# Door_PCB_MAIN.net
KiCad netlist of a schematic drawn in Altium Designer
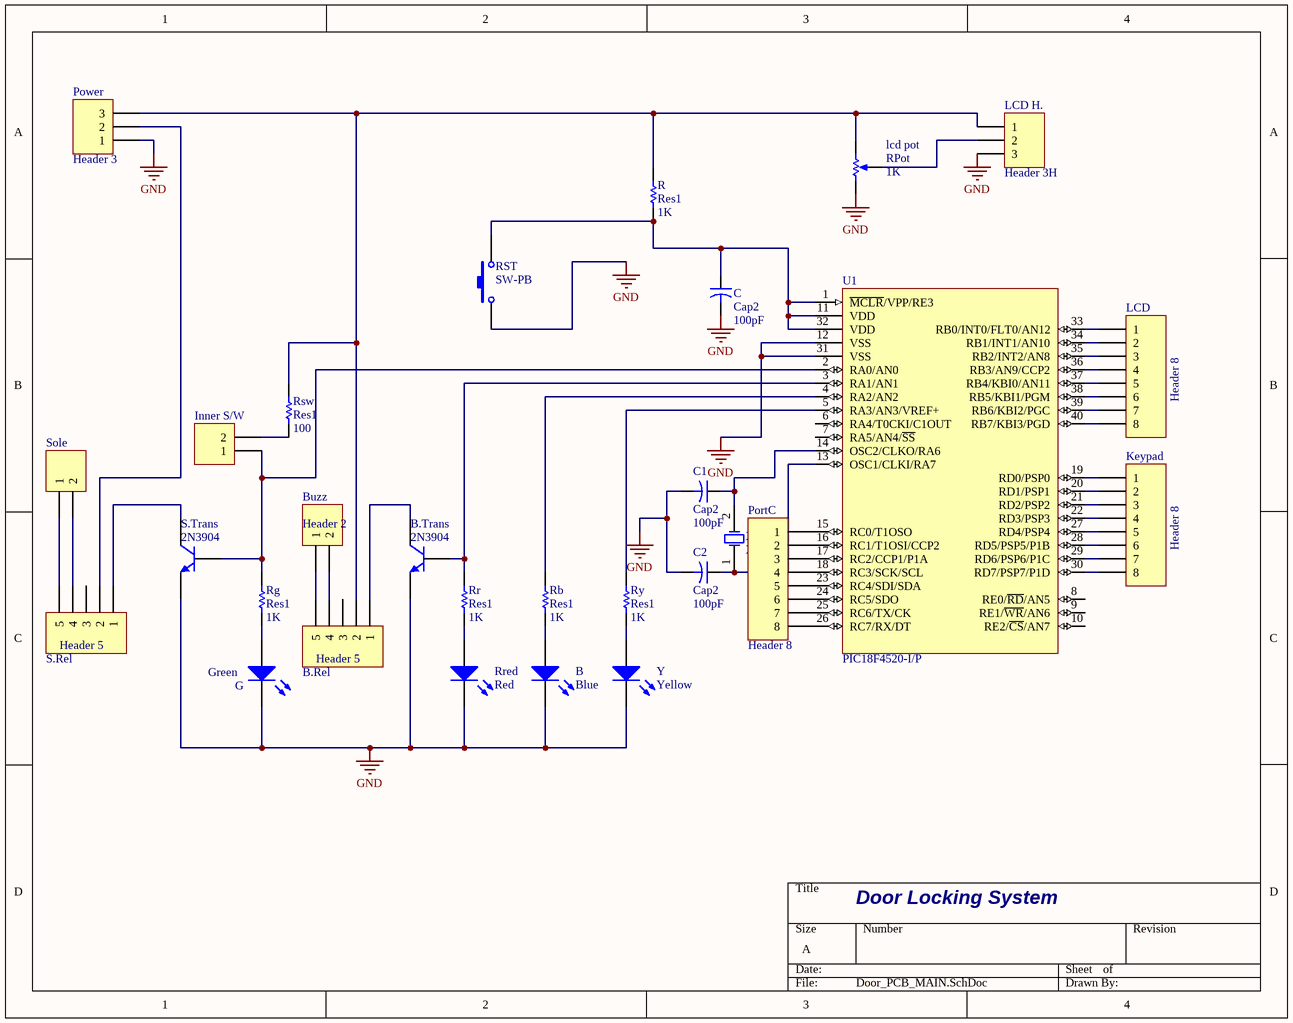
[diagram p0: Door_PCB_MAIN.SchDoc]

(export (version "E")
  (design (tool "Eeschema 10.0.6"))
  (components
    (comp (ref "B")
      (value "Blue")
      (footprint "LED-0")
      (description "Typical BLUE SiC LED")
      (fields (field (name "PUBLISHER") "Altium Limited"))
      (libsource (lib "Miscellaneous Devices") (part "LED3"))
    )
    (comp (ref "B.Rel")
      (value "Header 5")
      (footprint "relay")
      (description "Header, 5-Pin")
      (fields (field (name "PUBLISHER") "Altium Limited"))
      (libsource (lib "Miscellaneous Connectors") (part "Header 5"))
    )
    (comp (ref "B.Trans")
      (value "2N3904")
      (footprint "HDR1X3")
      (description "NPN General Purpose Amplifier")
      (fields (field (name "PUBLISHER") "Altium Limited"))
      (libsource (lib "Miscellaneous Devices") (part "2N3904"))
    )
    (comp (ref "Buzz")
      (value "Header 2")
      (footprint "HDR1X2")
      (description "Header, 2-Pin")
      (fields (field (name "PUBLISHER") "Altium Limited"))
      (libsource (lib "Miscellaneous Connectors") (part "Header 2"))
    )
    (comp (ref "C")
      (value "Cap2")
      (footprint "CAPR5-4X5")
      (description "Capacitor")
      (fields (field (name "ALTIUM_VALUE") "100pF") (field (name "PUBLISHER") "Altium Limited"))
      (libsource (lib "Miscellaneous_Devices") (part "Cap2"))
    )
    (comp (ref "C1")
      (value "Cap2")
      (footprint "CAPR5-4X5")
      (description "Capacitor")
      (fields (field (name "ALTIUM_VALUE") "100pF") (field (name "PUBLISHER") "Altium Limited"))
      (libsource (lib "Miscellaneous_Devices") (part "Cap2"))
    )
    (comp (ref "C2")
      (value "Cap2")
      (footprint "CAPR5-4X5")
      (description "Capacitor")
      (fields (field (name "ALTIUM_VALUE") "100pF") (field (name "PUBLISHER") "Altium Limited"))
      (libsource (lib "Miscellaneous_Devices") (part "Cap2"))
    )
    (comp (ref "G")
      (value "Green")
      (footprint "LED-0")
      (description "Typical RED, GREEN, YELLOW, AMBER GaAs LED")
      (fields (field (name "PUBLISHER") "Altium Limited"))
      (libsource (lib "Miscellaneous Devices") (part "LED2"))
    )
    (comp (ref "Inner S/W")
      (value "Header 2")
      (footprint "HDR1X2")
      (description "Header, 2-Pin")
      (fields (field (name "PUBLISHER") "Altium Limited"))
      (libsource (lib "") (part "Header 2_1"))
    )
    (comp (ref "Keypad")
      (value "Header 8")
      (footprint "HDR1X8")
      (description "Header, 8-Pin")
      (fields (field (name "PUBLISHER") "Altium Limited"))
      (libsource (lib "Miscellaneous Connectors") (part "Header 8"))
    )
    (comp (ref "LCD")
      (value "Header 8")
      (footprint "HDR1X8")
      (description "Header, 8-Pin")
      (fields (field (name "PUBLISHER") "Altium Limited"))
      (libsource (lib "Miscellaneous Connectors") (part "Header 8"))
    )
    (comp (ref "LCD H.")
      (value "Header 3H")
      (footprint "HDR1X3H")
      (description "Header, 3-Pin, Right Angle")
      (fields (field (name "PUBLISHER") "Altium Limited"))
      (libsource (lib "Miscellaneous_Connectors") (part "Header 3H"))
    )
    (comp (ref "lcd pot")
      (value "RPot")
      (footprint "VR5")
      (description "Potentiometer")
      (fields (field (name "ALTIUM_VALUE") "1K") (field (name "PUBLISHER") "Altium Limited"))
      (libsource (lib "Miscellaneous_Devices") (part "RPot"))
    )
    (comp (ref "PortC")
      (value "Header 8")
      (footprint "HDR1X8")
      (description "Header, 8-Pin")
      (fields (field (name "PUBLISHER") "Altium Limited"))
      (libsource (lib "Miscellaneous_Connectors") (part "Header 8"))
    )
    (comp (ref "Power")
      (value "Header 3")
      (footprint "HDR1X3")
      (description "Header, 3-Pin")
      (fields (field (name "PUBLISHER") "Altium Limited"))
      (libsource (lib "Miscellaneous Connectors") (part "Header 3"))
    )
    (comp (ref "R")
      (value "Res1")
      (footprint "AXIAL-0.3")
      (description "Resistor")
      (fields (field (name "ALTIUM_VALUE") "1K") (field (name "PUBLISHER") "Altium Limited"))
      (libsource (lib "Miscellaneous_Devices") (part "Res1"))
    )
    (comp (ref "Rb")
      (value "Res1")
      (footprint "AXIAL-0.3")
      (description "Resistor")
      (fields (field (name "ALTIUM_VALUE") "1K") (field (name "PUBLISHER") "Altium Limited"))
      (libsource (lib "Miscellaneous Devices") (part "Res1"))
    )
    (comp (ref "Rg")
      (value "Res1")
      (footprint "AXIAL-0.3")
      (description "Resistor")
      (fields (field (name "ALTIUM_VALUE") "1K") (field (name "PUBLISHER") "Altium Limited"))
      (libsource (lib "Miscellaneous Devices") (part "Res1"))
    )
    (comp (ref "Rr")
      (value "Res1")
      (footprint "AXIAL-0.3")
      (description "Resistor")
      (fields (field (name "ALTIUM_VALUE") "1K") (field (name "PUBLISHER") "Altium Limited"))
      (libsource (lib "Miscellaneous Devices") (part "Res1"))
    )
    (comp (ref "Rred")
      (value "Red")
      (footprint "LED-0")
      (description "Typical RED, GREEN, YELLOW, AMBER GaAs LED")
      (fields (field (name "PUBLISHER") "Altium Limited"))
      (libsource (lib "Miscellaneous Devices") (part "LED2"))
    )
    (comp (ref "RST")
      (value "SW-PB")
      (footprint "SPST-2")
      (description "Switch")
      (fields (field (name "PUBLISHER") "Altium Limited"))
      (libsource (lib "Miscellaneous_Devices") (part "SW-PB"))
    )
    (comp (ref "Rsw")
      (value "Res1")
      (footprint "AXIAL-0.3")
      (description "Resistor")
      (fields (field (name "ALTIUM_VALUE") "100") (field (name "PUBLISHER") "Altium Limited"))
      (libsource (lib "Miscellaneous Devices") (part "Res1"))
    )
    (comp (ref "Ry")
      (value "Res1")
      (footprint "AXIAL-0.3")
      (description "Resistor")
      (fields (field (name "ALTIUM_VALUE") "1K") (field (name "PUBLISHER") "Altium Limited"))
      (libsource (lib "Miscellaneous Devices") (part "Res1"))
    )
    (comp (ref "S.Rel")
      (value "Header 5")
      (footprint "relay")
      (description "Header, 5-Pin")
      (fields (field (name "PUBLISHER") "Altium Limited"))
      (libsource (lib "Miscellaneous Connectors") (part "Header 5"))
    )
    (comp (ref "S.Trans")
      (value "2N3904")
      (footprint "HDR1X3")
      (description "NPN General Purpose Amplifier")
      (fields (field (name "PUBLISHER") "Altium Limited"))
      (libsource (lib "Miscellaneous Devices") (part "2N3904"))
    )
    (comp (ref "Sole")
      (value "Header 2")
      (footprint "HDR1X2")
      (description "Header, 2-Pin")
      (fields (field (name "PUBLISHER") "Altium Limited"))
      (libsource (lib "Miscellaneous Connectors") (part "Header 2"))
    )
    (comp (ref "U1")
      (value "PIC18F4520-I/P")
      (footprint "PDIP600-P40")
      (fields (field (name "PUBLISHER") "Altium Limited"))
      (libsource (lib "Microchip Microcontroller 8-Bit PIC18") (part "PIC18F4520-I/P"))
    )
    (comp (ref "X")
      (value "XTAL")
      (footprint "R38")
      (description "Crystal Oscillator")
      (fields (field (name "PUBLISHER") "Altium Limited"))
      (libsource (lib "Miscellaneous_Devices") (part "XTAL"))
    )
    (comp (ref "Y")
      (value "Yellow")
      (footprint "LED-0")
      (description "Typical RED, GREEN, YELLOW, AMBER GaAs LED")
      (fields (field (name "PUBLISHER") "Altium Limited"))
      (libsource (lib "Miscellaneous Devices") (part "LED2"))
    )
  )
  (nets
    (net (code "1") (name "GND") (class "Default")
      (node (ref "B") (pin "2") (pinfunction "K_2") (pintype "passive"))
      (node (ref "B.Trans") (pin "1") (pinfunction "E_1") (pintype "passive"))
      (node (ref "C") (pin "2") (pinfunction "2_2") (pintype "passive"))
      (node (ref "C1") (pin "2") (pinfunction "2_2") (pintype "passive"))
      (node (ref "C2") (pin "2") (pinfunction "2_2") (pintype "passive"))
      (node (ref "G") (pin "2") (pinfunction "K_2") (pintype "passive"))
      (node (ref "LCD H.") (pin "3") (pinfunction "3_3") (pintype "passive"))
      (node (ref "Power") (pin "1") (pinfunction "1_1") (pintype "passive"))
      (node (ref "RST") (pin "1") (pinfunction "1_1") (pintype "passive"))
      (node (ref "Rred") (pin "2") (pinfunction "K_2") (pintype "passive"))
      (node (ref "S.Trans") (pin "1") (pinfunction "E_1") (pintype "passive"))
      (node (ref "U1") (pin "12") (pinfunction "VSS_12") (pintype "power_in"))
      (node (ref "U1") (pin "31") (pinfunction "VSS_31") (pintype "power_in"))
      (node (ref "Y") (pin "2") (pinfunction "K_2") (pintype "passive"))
      (node (ref "lcd pot") (pin "1") (pinfunction "TOP_1") (pintype "passive"))
    )
    (net (code "2") (name "Net-(B-A)") (class "Default")
      (node (ref "B") (pin "1") (pinfunction "A_1") (pintype "passive"))
      (node (ref "Rb") (pin "1") (pinfunction "1_1") (pintype "passive"))
    )
    (net (code "3") (name "Net-(B.Rel-Pad4)") (class "Default")
      (node (ref "B.Rel") (pin "4") (pinfunction "4_4") (pintype "passive"))
      (node (ref "Buzz") (pin "2") (pinfunction "2_2") (pintype "passive"))
    )
    (net (code "4") (name "Net-(B.Rel-Pad5)") (class "Default")
      (node (ref "B.Rel") (pin "5") (pinfunction "5_5") (pintype "passive"))
      (node (ref "Buzz") (pin "1") (pinfunction "1_1") (pintype "passive"))
    )
    (net (code "5") (name "Net-(B.Trans-B)") (class "Default")
      (node (ref "B.Trans") (pin "2") (pinfunction "B_2") (pintype "passive"))
      (node (ref "Rr") (pin "2") (pinfunction "2_2") (pintype "passive"))
      (node (ref "U1") (pin "3") (pinfunction "RA1/AN1_3") (pintype "bidirectional"))
    )
    (net (code "6") (name "Net-(B.Trans-C)") (class "Default")
      (node (ref "B.Rel") (pin "1") (pinfunction "1_1") (pintype "passive"))
      (node (ref "B.Trans") (pin "3") (pinfunction "C_3") (pintype "passive"))
    )
    (net (code "7") (name "Net-(G-A)") (class "Default")
      (node (ref "G") (pin "1") (pinfunction "A_1") (pintype "passive"))
      (node (ref "Rg") (pin "1") (pinfunction "1_1") (pintype "passive"))
    )
    (net (code "8") (name "Net-(Inner S/W-Pad2)") (class "Default")
      (node (ref "Inner S/W") (pin "2") (pinfunction "2_2") (pintype "passive"))
      (node (ref "Rsw") (pin "1") (pinfunction "1_1") (pintype "passive"))
    )
    (net (code "9") (name "Net-(Power-Pad2)") (class "Default")
      (node (ref "Power") (pin "2") (pinfunction "2_2") (pintype "passive"))
      (node (ref "S.Rel") (pin "2") (pinfunction "2_2") (pintype "passive"))
    )
    (net (code "10") (name "Net-(Rred-A)") (class "Default")
      (node (ref "Rr") (pin "1") (pinfunction "1_1") (pintype "passive"))
      (node (ref "Rred") (pin "1") (pinfunction "A_1") (pintype "passive"))
    )
    (net (code "11") (name "Net-(S.Rel-Pad4)") (class "Default")
      (node (ref "S.Rel") (pin "4") (pinfunction "4_4") (pintype "passive"))
      (node (ref "Sole") (pin "2") (pinfunction "2_2") (pintype "passive"))
    )
    (net (code "12") (name "Net-(S.Rel-Pad5)") (class "Default")
      (node (ref "S.Rel") (pin "5") (pinfunction "5_5") (pintype "passive"))
      (node (ref "Sole") (pin "1") (pinfunction "1_1") (pintype "passive"))
    )
    (net (code "13") (name "Net-(S.Trans-B)") (class "Default")
      (node (ref "Inner S/W") (pin "1") (pinfunction "1_1") (pintype "passive"))
      (node (ref "Rg") (pin "2") (pinfunction "2_2") (pintype "passive"))
      (node (ref "S.Trans") (pin "2") (pinfunction "B_2") (pintype "passive"))
      (node (ref "U1") (pin "2") (pinfunction "RA0/AN0_2") (pintype "bidirectional"))
    )
    (net (code "14") (name "Net-(S.Trans-C)") (class "Default")
      (node (ref "S.Rel") (pin "1") (pinfunction "1_1") (pintype "passive"))
      (node (ref "S.Trans") (pin "3") (pinfunction "C_3") (pintype "passive"))
    )
    (net (code "15") (name "Net-(U1-OSC1{slash}CLKI{slash}RA7)") (class "Default")
      (node (ref "C2") (pin "1") (pinfunction "1_1") (pintype "passive"))
      (node (ref "U1") (pin "13") (pinfunction "OSC1/CLKI/RA7_13") (pintype "bidirectional"))
      (node (ref "X") (pin "1") (pinfunction "OSC1_1") (pintype "passive"))
    )
    (net (code "16") (name "Net-(U1-OSC2{slash}CLKO{slash}RA6)") (class "Default")
      (node (ref "C1") (pin "1") (pinfunction "1_1") (pintype "passive"))
      (node (ref "U1") (pin "14") (pinfunction "OSC2/CLKO/RA6_14") (pintype "bidirectional"))
      (node (ref "X") (pin "2") (pinfunction "OSC2_2") (pintype "passive"))
    )
    (net (code "17") (name "Net-(U1-RA2{slash}AN2)") (class "Default")
      (node (ref "Rb") (pin "2") (pinfunction "2_2") (pintype "passive"))
      (node (ref "U1") (pin "4") (pinfunction "RA2/AN2_4") (pintype "bidirectional"))
    )
    (net (code "18") (name "Net-(U1-RA3{slash}AN3{slash}VREF+)") (class "Default")
      (node (ref "Ry") (pin "2") (pinfunction "2_2") (pintype "passive"))
      (node (ref "U1") (pin "5") (pinfunction "RA3/AN3/VREF+_5") (pintype "bidirectional"))
    )
    (net (code "19") (name "Net-(U1-RB0{slash}INT0{slash}FLT0{slash}AN12)") (class "Default")
      (node (ref "LCD") (pin "1") (pinfunction "1_1") (pintype "passive"))
      (node (ref "U1") (pin "33") (pinfunction "RB0/INT0/FLT0/AN12_33") (pintype "bidirectional"))
    )
    (net (code "20") (name "Net-(U1-RB1{slash}INT1{slash}AN10)") (class "Default")
      (node (ref "LCD") (pin "2") (pinfunction "2_2") (pintype "passive"))
      (node (ref "U1") (pin "34") (pinfunction "RB1/INT1/AN10_34") (pintype "bidirectional"))
    )
    (net (code "21") (name "Net-(U1-RB2{slash}INT2{slash}AN8)") (class "Default")
      (node (ref "LCD") (pin "3") (pinfunction "3_3") (pintype "passive"))
      (node (ref "U1") (pin "35") (pinfunction "RB2/INT2/AN8_35") (pintype "bidirectional"))
    )
    (net (code "22") (name "Net-(U1-RB3{slash}AN9{slash}CCP2)") (class "Default")
      (node (ref "LCD") (pin "4") (pinfunction "4_4") (pintype "passive"))
      (node (ref "U1") (pin "36") (pinfunction "RB3/AN9/CCP2_36") (pintype "bidirectional"))
    )
    (net (code "23") (name "Net-(U1-RB4{slash}KBI0{slash}AN11)") (class "Default")
      (node (ref "LCD") (pin "5") (pinfunction "5_5") (pintype "passive"))
      (node (ref "U1") (pin "37") (pinfunction "RB4/KBI0/AN11_37") (pintype "bidirectional"))
    )
    (net (code "24") (name "Net-(U1-RB5{slash}KBI1{slash}PGM)") (class "Default")
      (node (ref "LCD") (pin "6") (pinfunction "6_6") (pintype "passive"))
      (node (ref "U1") (pin "38") (pinfunction "RB5/KBI1/PGM_38") (pintype "bidirectional"))
    )
    (net (code "25") (name "Net-(U1-RB6{slash}KBI2{slash}PGC)") (class "Default")
      (node (ref "LCD") (pin "7") (pinfunction "7_7") (pintype "passive"))
      (node (ref "U1") (pin "39") (pinfunction "RB6/KBI2/PGC_39") (pintype "bidirectional"))
    )
    (net (code "26") (name "Net-(U1-RB7{slash}KBI3{slash}PGD)") (class "Default")
      (node (ref "LCD") (pin "8") (pinfunction "8_8") (pintype "passive"))
      (node (ref "U1") (pin "40") (pinfunction "RB7/KBI3/PGD_40") (pintype "bidirectional"))
    )
    (net (code "27") (name "Net-(U1-RC0{slash}T1OSO)") (class "Default")
      (node (ref "PortC") (pin "1") (pinfunction "1_1") (pintype "passive"))
      (node (ref "U1") (pin "15") (pinfunction "RC0/T1OSO_15") (pintype "bidirectional"))
    )
    (net (code "28") (name "Net-(U1-RC1{slash}T1OSI{slash}CCP2)") (class "Default")
      (node (ref "PortC") (pin "2") (pinfunction "2_2") (pintype "passive"))
      (node (ref "U1") (pin "16") (pinfunction "RC1/T1OSI/CCP2_16") (pintype "bidirectional"))
    )
    (net (code "29") (name "Net-(U1-RC2{slash}CCP1{slash}P1A)") (class "Default")
      (node (ref "PortC") (pin "3") (pinfunction "3_3") (pintype "passive"))
      (node (ref "U1") (pin "17") (pinfunction "RC2/CCP1/P1A_17") (pintype "bidirectional"))
    )
    (net (code "30") (name "Net-(U1-RC3{slash}SCK{slash}SCL)") (class "Default")
      (node (ref "PortC") (pin "4") (pinfunction "4_4") (pintype "passive"))
      (node (ref "U1") (pin "18") (pinfunction "RC3/SCK/SCL_18") (pintype "bidirectional"))
    )
    (net (code "31") (name "Net-(U1-RC4{slash}SDI{slash}SDA)") (class "Default")
      (node (ref "PortC") (pin "5") (pinfunction "5_5") (pintype "passive"))
      (node (ref "U1") (pin "23") (pinfunction "RC4/SDI/SDA_23") (pintype "bidirectional"))
    )
    (net (code "32") (name "Net-(U1-RC5{slash}SDO)") (class "Default")
      (node (ref "PortC") (pin "6") (pinfunction "6_6") (pintype "passive"))
      (node (ref "U1") (pin "24") (pinfunction "RC5/SDO_24") (pintype "bidirectional"))
    )
    (net (code "33") (name "Net-(U1-RC6{slash}TX{slash}CK)") (class "Default")
      (node (ref "PortC") (pin "7") (pinfunction "7_7") (pintype "passive"))
      (node (ref "U1") (pin "25") (pinfunction "RC6/TX/CK_25") (pintype "bidirectional"))
    )
    (net (code "34") (name "Net-(U1-RC7{slash}RX{slash}DT)") (class "Default")
      (node (ref "PortC") (pin "8") (pinfunction "8_8") (pintype "passive"))
      (node (ref "U1") (pin "26") (pinfunction "RC7/RX/DT_26") (pintype "bidirectional"))
    )
    (net (code "35") (name "Net-(U1-RD0{slash}PSP0)") (class "Default")
      (node (ref "Keypad") (pin "1") (pinfunction "1_1") (pintype "passive"))
      (node (ref "U1") (pin "19") (pinfunction "RD0/PSP0_19") (pintype "bidirectional"))
    )
    (net (code "36") (name "Net-(U1-RD1{slash}PSP1)") (class "Default")
      (node (ref "Keypad") (pin "2") (pinfunction "2_2") (pintype "passive"))
      (node (ref "U1") (pin "20") (pinfunction "RD1/PSP1_20") (pintype "bidirectional"))
    )
    (net (code "37") (name "Net-(U1-RD2{slash}PSP2)") (class "Default")
      (node (ref "Keypad") (pin "3") (pinfunction "3_3") (pintype "passive"))
      (node (ref "U1") (pin "21") (pinfunction "RD2/PSP2_21") (pintype "bidirectional"))
    )
    (net (code "38") (name "Net-(U1-RD3{slash}PSP3)") (class "Default")
      (node (ref "Keypad") (pin "4") (pinfunction "4_4") (pintype "passive"))
      (node (ref "U1") (pin "22") (pinfunction "RD3/PSP3_22") (pintype "bidirectional"))
    )
    (net (code "39") (name "Net-(U1-RD4{slash}PSP4)") (class "Default")
      (node (ref "Keypad") (pin "5") (pinfunction "5_5") (pintype "passive"))
      (node (ref "U1") (pin "27") (pinfunction "RD4/PSP4_27") (pintype "bidirectional"))
    )
    (net (code "40") (name "Net-(U1-RD5{slash}PSP5{slash}P1B)") (class "Default")
      (node (ref "Keypad") (pin "6") (pinfunction "6_6") (pintype "passive"))
      (node (ref "U1") (pin "28") (pinfunction "RD5/PSP5/P1B_28") (pintype "bidirectional"))
    )
    (net (code "41") (name "Net-(U1-RD6{slash}PSP6{slash}P1C)") (class "Default")
      (node (ref "Keypad") (pin "7") (pinfunction "7_7") (pintype "passive"))
      (node (ref "U1") (pin "29") (pinfunction "RD6/PSP6/P1C_29") (pintype "bidirectional"))
    )
    (net (code "42") (name "Net-(U1-RD7{slash}PSP7{slash}P1D)") (class "Default")
      (node (ref "Keypad") (pin "8") (pinfunction "8_8") (pintype "passive"))
      (node (ref "U1") (pin "30") (pinfunction "RD7/PSP7/P1D_30") (pintype "bidirectional"))
    )
    (net (code "43") (name "Net-(U1-~{MCLR}{slash}VPP{slash}RE3)") (class "Default")
      (node (ref "C") (pin "1") (pinfunction "1_1") (pintype "passive"))
      (node (ref "R") (pin "1") (pinfunction "1_1") (pintype "passive"))
      (node (ref "RST") (pin "2") (pinfunction "2_2") (pintype "passive"))
      (node (ref "U1") (pin "1") (pinfunction "~{MCLR}/VPP/RE3_1") (pintype "input"))
      (node (ref "U1") (pin "11") (pinfunction "VDD_11") (pintype "power_in"))
      (node (ref "U1") (pin "32") (pinfunction "VDD_32") (pintype "power_in"))
    )
    (net (code "44") (name "Net-(Y-A)") (class "Default")
      (node (ref "Ry") (pin "1") (pinfunction "1_1") (pintype "passive"))
      (node (ref "Y") (pin "1") (pinfunction "A_1") (pintype "passive"))
    )
    (net (code "45") (name "Net-(lcd pot-BOT)") (class "Default")
      (node (ref "B.Rel") (pin "2") (pinfunction "2_2") (pintype "passive"))
      (node (ref "LCD H.") (pin "1") (pinfunction "1_1") (pintype "passive"))
      (node (ref "Power") (pin "3") (pinfunction "3_3") (pintype "passive"))
      (node (ref "R") (pin "2") (pinfunction "2_2") (pintype "passive"))
      (node (ref "Rsw") (pin "2") (pinfunction "2_2") (pintype "passive"))
      (node (ref "lcd pot") (pin "2") (pinfunction "BOT_2") (pintype "passive"))
    )
    (net (code "46") (name "Net-(lcd pot-TAP)") (class "Default")
      (node (ref "LCD H.") (pin "2") (pinfunction "2_2") (pintype "passive"))
      (node (ref "lcd pot") (pin "3") (pinfunction "TAP_3") (pintype "passive"))
    )
    (net (code "47") (name "unconnected-(B.Rel-Pad3)") (class "Default")
      (node (ref "B.Rel") (pin "3") (pinfunction "3_3") (pintype "passive"))
    )
    (net (code "48") (name "unconnected-(S.Rel-Pad3)") (class "Default")
      (node (ref "S.Rel") (pin "3") (pinfunction "3_3") (pintype "passive"))
    )
    (net (code "49") (name "unconnected-(U1-RA4{slash}T0CKI{slash}C1OUT-Pad6)") (class "Default")
      (node (ref "U1") (pin "6") (pinfunction "RA4/T0CKI/C1OUT_6") (pintype "bidirectional"))
    )
    (net (code "50") (name "unconnected-(U1-RA5{slash}AN4{slash}~{SS}-Pad7)") (class "Default")
      (node (ref "U1") (pin "7") (pinfunction "RA5/AN4/~{SS}_7") (pintype "bidirectional"))
    )
    (net (code "51") (name "unconnected-(U1-RE0{slash}~{RD}{slash}AN5-Pad8)") (class "Default")
      (node (ref "U1") (pin "8") (pinfunction "RE0/~{RD}/AN5_8") (pintype "bidirectional"))
    )
    (net (code "52") (name "unconnected-(U1-RE1{slash}~{WR}{slash}AN6-Pad9)") (class "Default")
      (node (ref "U1") (pin "9") (pinfunction "RE1/~{WR}/AN6_9") (pintype "bidirectional"))
    )
    (net (code "53") (name "unconnected-(U1-RE2{slash}~{CS}{slash}AN7-Pad10)") (class "Default")
      (node (ref "U1") (pin "10") (pinfunction "RE2/~{CS}/AN7_10") (pintype "bidirectional"))
    )
  )
)
